# main.net
KiCad netlist of a schematic drawn in EAGLE
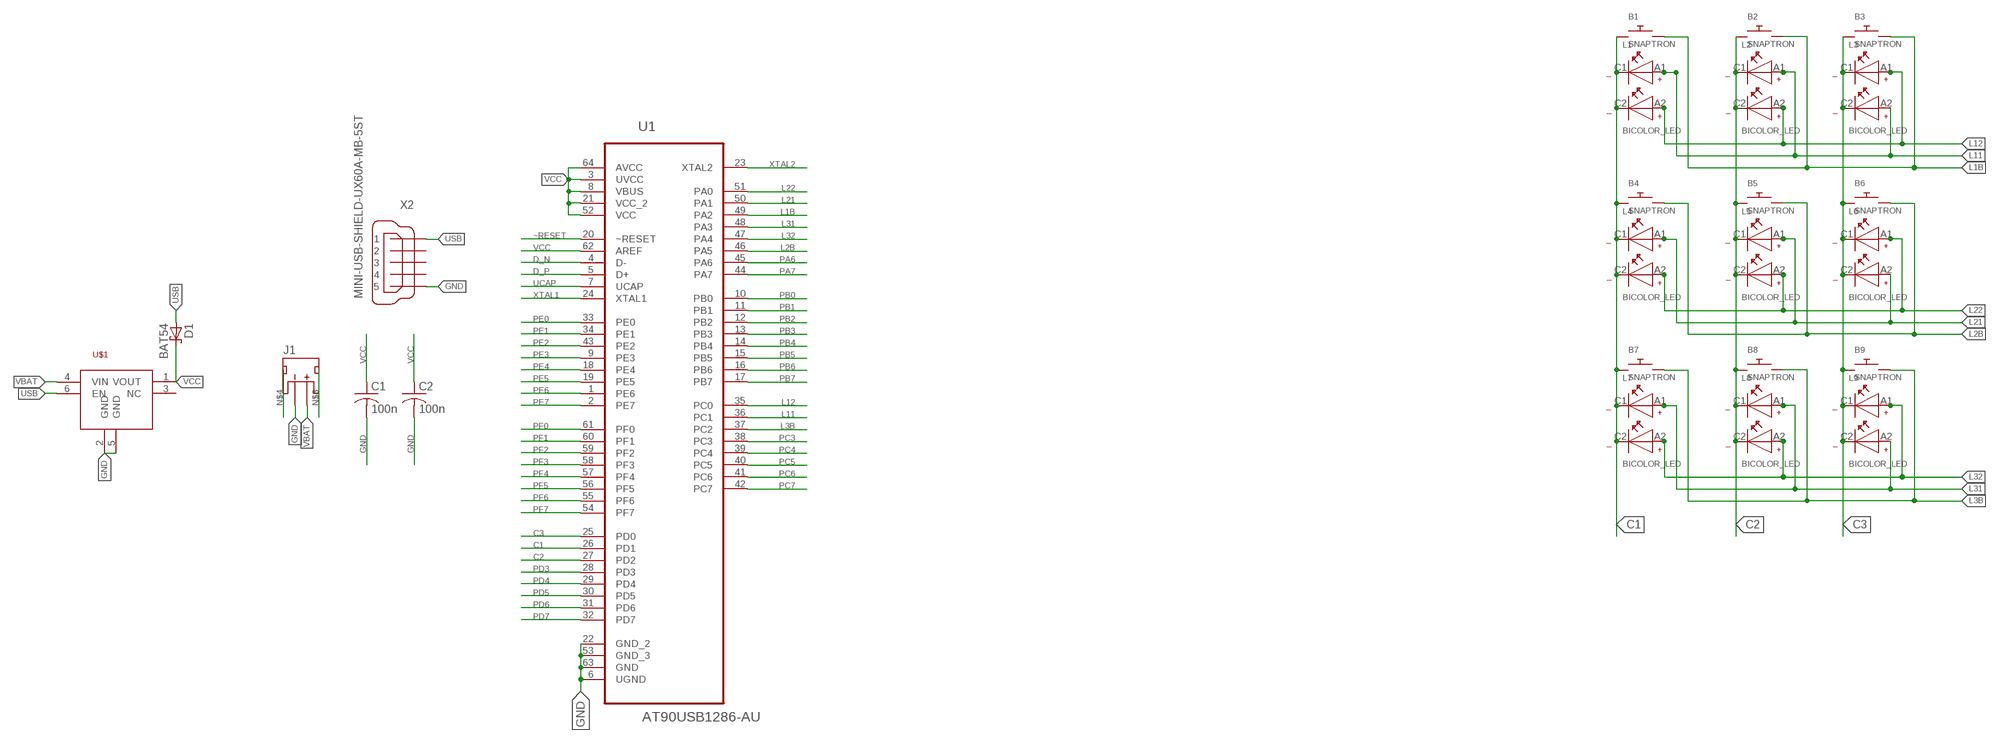
[diagram p0: schematic, sheet 1]

(export (version "E")
  (design (tool "Eeschema 10.0.6"))
  (components
    (comp (ref "B1")
      (value "SNAPTRON")
      (footprint "eagle-import:SNAPTRON-8.5")
      (libsource (lib "eagle-import") (part "SNAPTRON"))
    )
    (comp (ref "B2")
      (value "SNAPTRON")
      (footprint "eagle-import:SNAPTRON-8.5")
      (libsource (lib "eagle-import") (part "SNAPTRON"))
    )
    (comp (ref "B3")
      (value "SNAPTRON")
      (footprint "eagle-import:SNAPTRON-8.5")
      (libsource (lib "eagle-import") (part "SNAPTRON"))
    )
    (comp (ref "B4")
      (value "SNAPTRON")
      (footprint "eagle-import:SNAPTRON-8.5")
      (libsource (lib "eagle-import") (part "SNAPTRON"))
    )
    (comp (ref "B5")
      (value "SNAPTRON")
      (footprint "eagle-import:SNAPTRON-8.5")
      (libsource (lib "eagle-import") (part "SNAPTRON"))
    )
    (comp (ref "B6")
      (value "SNAPTRON")
      (footprint "eagle-import:SNAPTRON-8.5")
      (libsource (lib "eagle-import") (part "SNAPTRON"))
    )
    (comp (ref "B7")
      (value "SNAPTRON")
      (footprint "eagle-import:SNAPTRON-8.5")
      (libsource (lib "eagle-import") (part "SNAPTRON"))
    )
    (comp (ref "B8")
      (value "SNAPTRON")
      (footprint "eagle-import:SNAPTRON-8.5")
      (libsource (lib "eagle-import") (part "SNAPTRON"))
    )
    (comp (ref "B9")
      (value "SNAPTRON")
      (footprint "eagle-import:SNAPTRON-8.5")
      (libsource (lib "eagle-import") (part "SNAPTRON"))
    )
    (comp (ref "C1")
      (value "100n")
      (footprint "eagle-import:C0603")
      (libsource (lib "eagle-import") (part "C-USC0603"))
    )
    (comp (ref "C2")
      (value "100n")
      (footprint "eagle-import:C0603")
      (libsource (lib "eagle-import") (part "C-USC0603"))
    )
    (comp (ref "D1")
      (value "BAT54")
      (footprint "eagle-import:SOT23")
      (libsource (lib "eagle-import") (part "BAT54"))
    )
    (comp (ref "J1")
      (value "JST_2MM_MALE")
      (footprint "eagle-import:JST-2-SMD")
      (libsource (lib "eagle-import") (part "JST_2MM_MALE"))
    )
    (comp (ref "L1")
      (value "BICOLOR_LED")
      (footprint "eagle-import:BICOLOR_LED")
      (libsource (lib "eagle-import") (part "BICOLOR_LED"))
    )
    (comp (ref "L2")
      (value "BICOLOR_LED")
      (footprint "eagle-import:BICOLOR_LED")
      (libsource (lib "eagle-import") (part "BICOLOR_LED"))
    )
    (comp (ref "L3")
      (value "BICOLOR_LED")
      (footprint "eagle-import:BICOLOR_LED")
      (libsource (lib "eagle-import") (part "BICOLOR_LED"))
    )
    (comp (ref "L4")
      (value "BICOLOR_LED")
      (footprint "eagle-import:BICOLOR_LED")
      (libsource (lib "eagle-import") (part "BICOLOR_LED"))
    )
    (comp (ref "L5")
      (value "BICOLOR_LED")
      (footprint "eagle-import:BICOLOR_LED")
      (libsource (lib "eagle-import") (part "BICOLOR_LED"))
    )
    (comp (ref "L6")
      (value "BICOLOR_LED")
      (footprint "eagle-import:BICOLOR_LED")
      (libsource (lib "eagle-import") (part "BICOLOR_LED"))
    )
    (comp (ref "L7")
      (value "BICOLOR_LED")
      (footprint "eagle-import:BICOLOR_LED")
      (libsource (lib "eagle-import") (part "BICOLOR_LED"))
    )
    (comp (ref "L8")
      (value "BICOLOR_LED")
      (footprint "eagle-import:BICOLOR_LED")
      (libsource (lib "eagle-import") (part "BICOLOR_LED"))
    )
    (comp (ref "L9")
      (value "BICOLOR_LED")
      (footprint "eagle-import:BICOLOR_LED")
      (libsource (lib "eagle-import") (part "BICOLOR_LED"))
    )
    (comp (ref "U$1")
      (value "MIC94090")
      (footprint "eagle-import:SC70-6L")
      (libsource (lib "eagle-import") (part "MIC94090"))
    )
    (comp (ref "U1")
      (value "AT90USB1286-AU")
      (footprint "eagle-import:QFP80P1600X1600X120-64N")
      (libsource (lib "eagle-import") (part "AT90USB1286-AU"))
    )
    (comp (ref "X2")
      (value "MINI-USB-SHIELD-UX60A-MB-5ST")
      (footprint "eagle-import:UX60A-MB-5ST")
      (libsource (lib "eagle-import") (part "MINI-USB-SHIELD-UX60A-MB-5ST"))
    )
  )
  (nets
    (net (code "1") (name "/D_N") (class "Default")
      (node (ref "U1") (pin "4") (pinfunction "D-_4") (pintype "input"))
    )
    (net (code "2") (name "/D_P") (class "Default")
      (node (ref "U1") (pin "5") (pinfunction "D+_5") (pintype "input"))
    )
    (net (code "3") (name "/N$3") (class "Default")
      (node (ref "J1") (pin "NC2") (pinfunction "PAD2_NC2") (pintype "bidirectional"))
    )
    (net (code "4") (name "/N$4") (class "Default")
      (node (ref "J1") (pin "NC1") (pinfunction "PAD1_NC1") (pintype "bidirectional"))
    )
    (net (code "5") (name "/PA6") (class "Default")
      (node (ref "U1") (pin "45") (pinfunction "PA6_45") (pintype "bidirectional"))
    )
    (net (code "6") (name "/PA7") (class "Default")
      (node (ref "U1") (pin "44") (pinfunction "PA7_44") (pintype "bidirectional"))
    )
    (net (code "7") (name "/PB0") (class "Default")
      (node (ref "U1") (pin "10") (pinfunction "PB0_10") (pintype "bidirectional"))
    )
    (net (code "8") (name "/PB1") (class "Default")
      (node (ref "U1") (pin "11") (pinfunction "PB1_11") (pintype "bidirectional"))
    )
    (net (code "9") (name "/PB2") (class "Default")
      (node (ref "U1") (pin "12") (pinfunction "PB2_12") (pintype "bidirectional"))
    )
    (net (code "10") (name "/PB3") (class "Default")
      (node (ref "U1") (pin "13") (pinfunction "PB3_13") (pintype "bidirectional"))
    )
    (net (code "11") (name "/PB4") (class "Default")
      (node (ref "U1") (pin "14") (pinfunction "PB4_14") (pintype "bidirectional"))
    )
    (net (code "12") (name "/PB5") (class "Default")
      (node (ref "U1") (pin "15") (pinfunction "PB5_15") (pintype "bidirectional"))
    )
    (net (code "13") (name "/PB6") (class "Default")
      (node (ref "U1") (pin "16") (pinfunction "PB6_16") (pintype "bidirectional"))
    )
    (net (code "14") (name "/PB7") (class "Default")
      (node (ref "U1") (pin "17") (pinfunction "PB7_17") (pintype "bidirectional"))
    )
    (net (code "15") (name "/PC3") (class "Default")
      (node (ref "U1") (pin "38") (pinfunction "PC3_38") (pintype "bidirectional"))
    )
    (net (code "16") (name "/PC4") (class "Default")
      (node (ref "U1") (pin "39") (pinfunction "PC4_39") (pintype "bidirectional"))
    )
    (net (code "17") (name "/PC5") (class "Default")
      (node (ref "U1") (pin "40") (pinfunction "PC5_40") (pintype "bidirectional"))
    )
    (net (code "18") (name "/PC6") (class "Default")
      (node (ref "U1") (pin "41") (pinfunction "PC6_41") (pintype "bidirectional"))
    )
    (net (code "19") (name "/PC7") (class "Default")
      (node (ref "U1") (pin "42") (pinfunction "PC7_42") (pintype "bidirectional"))
    )
    (net (code "20") (name "/PD3") (class "Default")
      (node (ref "U1") (pin "28") (pinfunction "PD3_28") (pintype "bidirectional"))
    )
    (net (code "21") (name "/PD4") (class "Default")
      (node (ref "U1") (pin "29") (pinfunction "PD4_29") (pintype "bidirectional"))
    )
    (net (code "22") (name "/PD5") (class "Default")
      (node (ref "U1") (pin "30") (pinfunction "PD5_30") (pintype "bidirectional"))
    )
    (net (code "23") (name "/PD6") (class "Default")
      (node (ref "U1") (pin "31") (pinfunction "PD6_31") (pintype "bidirectional"))
    )
    (net (code "24") (name "/PD7") (class "Default")
      (node (ref "U1") (pin "32") (pinfunction "PD7_32") (pintype "bidirectional"))
    )
    (net (code "25") (name "/PE0") (class "Default")
      (node (ref "U1") (pin "33") (pinfunction "PE0_33") (pintype "bidirectional"))
    )
    (net (code "26") (name "/PE1") (class "Default")
      (node (ref "U1") (pin "34") (pinfunction "PE1_34") (pintype "bidirectional"))
    )
    (net (code "27") (name "/PE2") (class "Default")
      (node (ref "U1") (pin "43") (pinfunction "PE2_43") (pintype "bidirectional"))
    )
    (net (code "28") (name "/PE3") (class "Default")
      (node (ref "U1") (pin "9") (pinfunction "PE3_9") (pintype "bidirectional"))
    )
    (net (code "29") (name "/PE4") (class "Default")
      (node (ref "U1") (pin "18") (pinfunction "PE4_18") (pintype "bidirectional"))
    )
    (net (code "30") (name "/PE5") (class "Default")
      (node (ref "U1") (pin "19") (pinfunction "PE5_19") (pintype "bidirectional"))
    )
    (net (code "31") (name "/PE6") (class "Default")
      (node (ref "U1") (pin "1") (pinfunction "PE6_1") (pintype "bidirectional"))
    )
    (net (code "32") (name "/PE7") (class "Default")
      (node (ref "U1") (pin "2") (pinfunction "PE7_2") (pintype "bidirectional"))
    )
    (net (code "33") (name "/PF0") (class "Default")
      (node (ref "U1") (pin "61") (pinfunction "PF0_61") (pintype "bidirectional"))
    )
    (net (code "34") (name "/PF1") (class "Default")
      (node (ref "U1") (pin "60") (pinfunction "PF1_60") (pintype "bidirectional"))
    )
    (net (code "35") (name "/PF2") (class "Default")
      (node (ref "U1") (pin "59") (pinfunction "PF2_59") (pintype "bidirectional"))
    )
    (net (code "36") (name "/PF3") (class "Default")
      (node (ref "U1") (pin "58") (pinfunction "PF3_58") (pintype "bidirectional"))
    )
    (net (code "37") (name "/PF4") (class "Default")
      (node (ref "U1") (pin "57") (pinfunction "PF4_57") (pintype "bidirectional"))
    )
    (net (code "38") (name "/PF5") (class "Default")
      (node (ref "U1") (pin "56") (pinfunction "PF5_56") (pintype "bidirectional"))
    )
    (net (code "39") (name "/PF6") (class "Default")
      (node (ref "U1") (pin "55") (pinfunction "PF6_55") (pintype "bidirectional"))
    )
    (net (code "40") (name "/PF7") (class "Default")
      (node (ref "U1") (pin "54") (pinfunction "PF7_54") (pintype "bidirectional"))
    )
    (net (code "41") (name "/UCAP") (class "Default")
      (node (ref "U1") (pin "7") (pinfunction "UCAP_7") (pintype "passive"))
    )
    (net (code "42") (name "/XTAL1") (class "Default")
      (node (ref "U1") (pin "24") (pinfunction "XTAL1_24") (pintype "input"))
    )
    (net (code "43") (name "/XTAL2") (class "Default")
      (node (ref "U1") (pin "23") (pinfunction "XTAL2_23") (pintype "output"))
    )
    (net (code "44") (name "/~{RESET}") (class "Default")
      (node (ref "U1") (pin "20") (pinfunction "~{RESET}_20") (pintype "input"))
    )
    (net (code "45") (name "C1") (class "Default")
      (node (ref "B1") (pin "P$1") (pinfunction "P$1_P$1") (pintype "passive"))
      (node (ref "B4") (pin "P$1") (pinfunction "P$1_P$1") (pintype "passive"))
      (node (ref "B7") (pin "P$1") (pinfunction "P$1_P$1") (pintype "passive"))
      (node (ref "L1") (pin "C1") (pinfunction "C1_C1") (pintype "passive"))
      (node (ref "L1") (pin "C2") (pinfunction "C2_C2") (pintype "passive"))
      (node (ref "L4") (pin "C1") (pinfunction "C1_C1") (pintype "passive"))
      (node (ref "L4") (pin "C2") (pinfunction "C2_C2") (pintype "passive"))
      (node (ref "L7") (pin "C1") (pinfunction "C1_C1") (pintype "passive"))
      (node (ref "L7") (pin "C2") (pinfunction "C2_C2") (pintype "passive"))
      (node (ref "U1") (pin "26") (pinfunction "PD1_26") (pintype "bidirectional"))
    )
    (net (code "46") (name "C2") (class "Default")
      (node (ref "B2") (pin "P$1") (pinfunction "P$1_P$1") (pintype "passive"))
      (node (ref "B5") (pin "P$1") (pinfunction "P$1_P$1") (pintype "passive"))
      (node (ref "B8") (pin "P$1") (pinfunction "P$1_P$1") (pintype "passive"))
      (node (ref "L2") (pin "C1") (pinfunction "C1_C1") (pintype "passive"))
      (node (ref "L2") (pin "C2") (pinfunction "C2_C2") (pintype "passive"))
      (node (ref "L5") (pin "C1") (pinfunction "C1_C1") (pintype "passive"))
      (node (ref "L5") (pin "C2") (pinfunction "C2_C2") (pintype "passive"))
      (node (ref "L8") (pin "C1") (pinfunction "C1_C1") (pintype "passive"))
      (node (ref "L8") (pin "C2") (pinfunction "C2_C2") (pintype "passive"))
      (node (ref "U1") (pin "27") (pinfunction "PD2_27") (pintype "bidirectional"))
    )
    (net (code "47") (name "C3") (class "Default")
      (node (ref "B3") (pin "P$1") (pinfunction "P$1_P$1") (pintype "passive"))
      (node (ref "B6") (pin "P$1") (pinfunction "P$1_P$1") (pintype "passive"))
      (node (ref "B9") (pin "P$1") (pinfunction "P$1_P$1") (pintype "passive"))
      (node (ref "L3") (pin "C1") (pinfunction "C1_C1") (pintype "passive"))
      (node (ref "L3") (pin "C2") (pinfunction "C2_C2") (pintype "passive"))
      (node (ref "L6") (pin "C1") (pinfunction "C1_C1") (pintype "passive"))
      (node (ref "L6") (pin "C2") (pinfunction "C2_C2") (pintype "passive"))
      (node (ref "L9") (pin "C1") (pinfunction "C1_C1") (pintype "passive"))
      (node (ref "L9") (pin "C2") (pinfunction "C2_C2") (pintype "passive"))
      (node (ref "U1") (pin "25") (pinfunction "PD0_25") (pintype "bidirectional"))
    )
    (net (code "48") (name "GND") (class "Default")
      (node (ref "C1") (pin "2") (pinfunction "2_2") (pintype "passive"))
      (node (ref "C2") (pin "2") (pinfunction "2_2") (pintype "passive"))
      (node (ref "J1") (pin "1") (pinfunction "-_1") (pintype "bidirectional"))
      (node (ref "U$1") (pin "2") (pinfunction "GND_2") (pintype "bidirectional"))
      (node (ref "U$1") (pin "5") (pinfunction "GND_5") (pintype "bidirectional"))
      (node (ref "U1") (pin "22") (pinfunction "GND_2_22") (pintype "passive"))
      (node (ref "U1") (pin "53") (pinfunction "GND_3_53") (pintype "passive"))
      (node (ref "U1") (pin "6") (pinfunction "UGND_6") (pintype "passive"))
      (node (ref "U1") (pin "63") (pinfunction "GND_63") (pintype "passive"))
      (node (ref "X2") (pin "5") (pinfunction "5_5") (pintype "input"))
    )
    (net (code "49") (name "L1B") (class "Default")
      (node (ref "B1") (pin "P$2") (pinfunction "P$2_P$2") (pintype "passive"))
      (node (ref "B2") (pin "P$2") (pinfunction "P$2_P$2") (pintype "passive"))
      (node (ref "B3") (pin "P$2") (pinfunction "P$2_P$2") (pintype "passive"))
      (node (ref "U1") (pin "49") (pinfunction "PA2_49") (pintype "bidirectional"))
    )
    (net (code "50") (name "L2B") (class "Default")
      (node (ref "B4") (pin "P$2") (pinfunction "P$2_P$2") (pintype "passive"))
      (node (ref "B5") (pin "P$2") (pinfunction "P$2_P$2") (pintype "passive"))
      (node (ref "B6") (pin "P$2") (pinfunction "P$2_P$2") (pintype "passive"))
      (node (ref "U1") (pin "46") (pinfunction "PA5_46") (pintype "bidirectional"))
    )
    (net (code "51") (name "L3B") (class "Default")
      (node (ref "B7") (pin "P$2") (pinfunction "P$2_P$2") (pintype "passive"))
      (node (ref "B8") (pin "P$2") (pinfunction "P$2_P$2") (pintype "passive"))
      (node (ref "B9") (pin "P$2") (pinfunction "P$2_P$2") (pintype "passive"))
      (node (ref "U1") (pin "37") (pinfunction "PC2_37") (pintype "bidirectional"))
    )
    (net (code "52") (name "L11") (class "Default")
      (node (ref "L1") (pin "A1") (pinfunction "A1_A1") (pintype "passive"))
      (node (ref "L2") (pin "A1") (pinfunction "A1_A1") (pintype "passive"))
      (node (ref "L3") (pin "A2") (pinfunction "A2_A2") (pintype "passive"))
      (node (ref "U1") (pin "36") (pinfunction "PC1_36") (pintype "bidirectional"))
    )
    (net (code "53") (name "L12") (class "Default")
      (node (ref "L1") (pin "A2") (pinfunction "A2_A2") (pintype "passive"))
      (node (ref "L2") (pin "A2") (pinfunction "A2_A2") (pintype "passive"))
      (node (ref "L3") (pin "A1") (pinfunction "A1_A1") (pintype "passive"))
      (node (ref "U1") (pin "35") (pinfunction "PC0_35") (pintype "bidirectional"))
    )
    (net (code "54") (name "L21") (class "Default")
      (node (ref "L4") (pin "A1") (pinfunction "A1_A1") (pintype "passive"))
      (node (ref "L5") (pin "A1") (pinfunction "A1_A1") (pintype "passive"))
      (node (ref "L6") (pin "A2") (pinfunction "A2_A2") (pintype "passive"))
      (node (ref "U1") (pin "50") (pinfunction "PA1_50") (pintype "bidirectional"))
    )
    (net (code "55") (name "L22") (class "Default")
      (node (ref "L4") (pin "A2") (pinfunction "A2_A2") (pintype "passive"))
      (node (ref "L5") (pin "A2") (pinfunction "A2_A2") (pintype "passive"))
      (node (ref "L6") (pin "A1") (pinfunction "A1_A1") (pintype "passive"))
      (node (ref "U1") (pin "51") (pinfunction "PA0_51") (pintype "bidirectional"))
    )
    (net (code "56") (name "L31") (class "Default")
      (node (ref "L7") (pin "A1") (pinfunction "A1_A1") (pintype "passive"))
      (node (ref "L8") (pin "A1") (pinfunction "A1_A1") (pintype "passive"))
      (node (ref "L9") (pin "A2") (pinfunction "A2_A2") (pintype "passive"))
      (node (ref "U1") (pin "48") (pinfunction "PA3_48") (pintype "bidirectional"))
    )
    (net (code "57") (name "L32") (class "Default")
      (node (ref "L7") (pin "A2") (pinfunction "A2_A2") (pintype "passive"))
      (node (ref "L8") (pin "A2") (pinfunction "A2_A2") (pintype "passive"))
      (node (ref "L9") (pin "A1") (pinfunction "A1_A1") (pintype "passive"))
      (node (ref "U1") (pin "47") (pinfunction "PA4_47") (pintype "bidirectional"))
    )
    (net (code "58") (name "USB") (class "Default")
      (node (ref "D1") (pin "1") (pinfunction "A_1") (pintype "passive"))
      (node (ref "U$1") (pin "6") (pinfunction "EN_6") (pintype "bidirectional"))
      (node (ref "X2") (pin "1") (pinfunction "1_1") (pintype "input"))
    )
    (net (code "59") (name "VBAT") (class "Default")
      (node (ref "J1") (pin "2") (pinfunction "+_2") (pintype "bidirectional"))
      (node (ref "U$1") (pin "4") (pinfunction "VIN_4") (pintype "bidirectional"))
    )
    (net (code "60") (name "VCC") (class "Default")
      (node (ref "C1") (pin "1") (pinfunction "1_1") (pintype "passive"))
      (node (ref "C2") (pin "1") (pinfunction "1_1") (pintype "passive"))
      (node (ref "D1") (pin "3") (pinfunction "C_3") (pintype "passive"))
      (node (ref "U$1") (pin "1") (pinfunction "VOUT_1") (pintype "bidirectional"))
      (node (ref "U1") (pin "21") (pinfunction "VCC_2_21") (pintype "power_in"))
      (node (ref "U1") (pin "3") (pinfunction "UVCC_3") (pintype "power_in"))
      (node (ref "U1") (pin "52") (pinfunction "VCC_52") (pintype "power_in"))
      (node (ref "U1") (pin "62") (pinfunction "AREF_62") (pintype "input"))
      (node (ref "U1") (pin "64") (pinfunction "AVCC_64") (pintype "power_in"))
      (node (ref "U1") (pin "8") (pinfunction "VBUS_8") (pintype "power_in"))
    )
    (net (code "61") (name "unconnected-(U$1-NC-Pad3)") (class "Default")
      (node (ref "U$1") (pin "3") (pinfunction "NC_3") (pintype "bidirectional"))
    )
    (net (code "62") (name "unconnected-(X2-Pad2)") (class "Default")
      (node (ref "X2") (pin "2") (pinfunction "2_2") (pintype "input"))
    )
    (net (code "63") (name "unconnected-(X2-Pad3)") (class "Default")
      (node (ref "X2") (pin "3") (pinfunction "3_3") (pintype "input"))
    )
    (net (code "64") (name "unconnected-(X2-Pad4)") (class "Default")
      (node (ref "X2") (pin "4") (pinfunction "4_4") (pintype "input"))
    )
  )
)
